# ESP32_C6_Schematic.net
KiCad netlist of a schematic drawn in Altium Designer
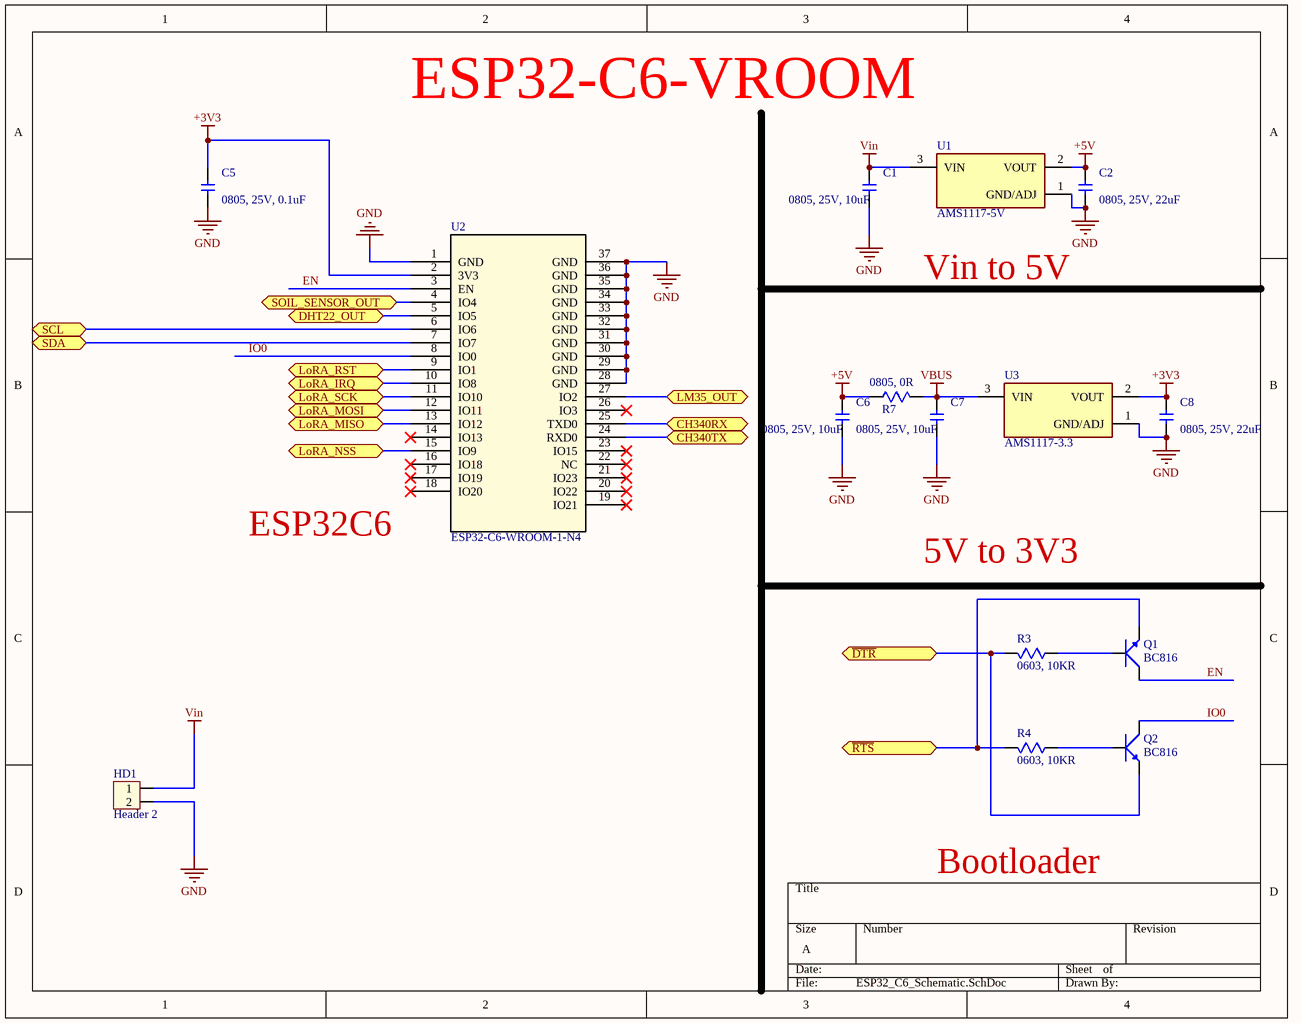
[diagram p0: ESP32_C6_Schematic.SchDoc]

(export (version "E")
  (design (tool "Eeschema 10.0.6"))
  (components
    (comp (ref "C1")
      (value "0805, 25V, 10uF")
      (footprint "C0805")
      (description "C0805")
      (libsource (lib "STM32F103 Blue Pill Library") (part "C0805"))
    )
    (comp (ref "C2")
      (value "0805, 25V, 22uF")
      (footprint "C0805")
      (description "C0805")
      (libsource (lib "STM32F103 Blue Pill Library") (part "C0805"))
    )
    (comp (ref "C5")
      (value "0805, 25V, 0.1uF")
      (footprint "C0805")
      (description "C0805")
      (libsource (lib "STM32F103 Blue Pill Library") (part "C0805"))
    )
    (comp (ref "C6")
      (value "0805, 25V, 10uF")
      (footprint "C0805")
      (description "C0805")
      (libsource (lib "STM32F103 Blue Pill Library") (part "C0805"))
    )
    (comp (ref "C7")
      (value "0805, 25V, 10uF")
      (footprint "C0805")
      (description "C0805")
      (libsource (lib "STM32F103 Blue Pill Library") (part "C0805"))
    )
    (comp (ref "C8")
      (value "0805, 25V, 22uF")
      (footprint "C0805")
      (description "C0805")
      (libsource (lib "STM32F103 Blue Pill Library") (part "C0805"))
    )
    (comp (ref "HD1")
      (value "Header 2")
      (footprint "HED2")
      (description "Header 2 (Green)")
      (libsource (lib "My Library") (part "Hed2"))
    )
    (comp (ref "Q1")
      (value "BC816")
      (footprint "SOT95P237X111-3N")
      (description "Transistor NPN 45V 0.5A hfe160 SOT23 ¦ ON Semiconductor BC817-25LT1G")
      (fields (field (name "MF") "ON Semiconductor") (field (name "MP") "BC817-25LT1G"))
      (libsource (lib "ESP_LoRa_schematic_lib") (part "BC816"))
    )
    (comp (ref "Q2")
      (value "BC816")
      (footprint "SOT95P237X111-3N")
      (description "Transistor NPN 45V 0.5A hfe160 SOT23 ¦ ON Semiconductor BC817-25LT1G")
      (fields (field (name "MF") "ON Semiconductor") (field (name "MP") "BC817-25LT1G"))
      (libsource (lib "ESP_LoRa_schematic_lib") (part "BC816"))
    )
    (comp (ref "R3")
      (value "0603, 10KR")
      (footprint "RES0603")
      (description "R0603")
      (libsource (lib "STM32F103 Blue Pill Library") (part "R0603"))
    )
    (comp (ref "R4")
      (value "0603, 10KR")
      (footprint "RES0603")
      (description "R0603")
      (libsource (lib "STM32F103 Blue Pill Library") (part "R0603"))
    )
    (comp (ref "R7")
      (value "0805, 0R")
      (footprint "C0805")
      (description "R0805")
      (libsource (lib "STM32F103 Blue Pill Library") (part "R0805"))
    )
    (comp (ref "U1")
      (value "AMS1117-5V")
      (footprint "SOT229P700X180-4N")
      (description "Sot223/Pkg 1-Amp 5V-Volt Low Drop Out Voltage Regulatator")
      (fields (field (name "MF") "Advanced Monolithic Systems") (field (name "MP") "AMS1117-3.3"))
      (libsource (lib "ESP_LoRa_schematic_lib") (part "AMS1117-5V"))
    )
    (comp (ref "U2")
      (value "ESP32-C6-WROOM-1-N4")
      (footprint "MOD28_ESP32-C6-WROOM-1_EXP")
      (description "Description")
      (fields (field (name "COPYRIGHT") "Copyright (C) 2025 Ultra Librarian. All rights reserved."))
      (libsource (lib "ESP_LoRa_schematic_lib") (part "ESP32-C6-WROOM-1-N4"))
    )
    (comp (ref "U3")
      (value "AMS1117-3.3")
      (footprint "SOT229P700X180-4N")
      (description "Sot223/Pkg 1-Amp 3.3-Volt Low Drop Out Voltage Regulatator")
      (fields (field (name "MF") "Advanced Monolithic Systems"))
      (libsource (lib "ESP_LoRa_schematic_lib") (part "AMS1117-3.3"))
    )
  )
  (nets
    (net (code "1") (name "+3V3") (class "Default")
      (node (ref "C5") (pin "2") (pinfunction "2_2") (pintype "passive"))
      (node (ref "C8") (pin "2") (pinfunction "2_2") (pintype "passive"))
      (node (ref "U2") (pin "2") (pinfunction "3V3_2") (pintype "passive"))
      (node (ref "U3") (pin "2") (pinfunction "VOUT_2") (pintype "passive"))
    )
    (net (code "2") (name "+5V") (class "Default")
      (node (ref "C2") (pin "2") (pinfunction "2_2") (pintype "passive"))
      (node (ref "C6") (pin "2") (pinfunction "2_2") (pintype "passive"))
      (node (ref "R7") (pin "1") (pinfunction "1_1") (pintype "passive"))
      (node (ref "U1") (pin "2") (pinfunction "VOUT_2") (pintype "passive"))
    )
    (net (code "3") (name "/CH340RX") (class "Default")
      (node (ref "U2") (pin "25") (pinfunction "TXD0_25") (pintype "passive"))
    )
    (net (code "4") (name "/CH340TX") (class "Default")
      (node (ref "U2") (pin "24") (pinfunction "RXD0_24") (pintype "passive"))
    )
    (net (code "5") (name "/DHT22_OUT") (class "Default")
      (node (ref "U2") (pin "5") (pinfunction "IO5_5") (pintype "passive"))
    )
    (net (code "6") (name "/EN") (class "Default")
      (node (ref "Q1") (pin "3") (pinfunction "C_3") (pintype "passive"))
      (node (ref "U2") (pin "3") (pinfunction "EN_3") (pintype "passive"))
    )
    (net (code "7") (name "/IO0") (class "Default")
      (node (ref "Q2") (pin "3") (pinfunction "C_3") (pintype "passive"))
      (node (ref "U2") (pin "8") (pinfunction "IO0_8") (pintype "passive"))
    )
    (net (code "8") (name "/LM35_OUT") (class "Default")
      (node (ref "U2") (pin "27") (pinfunction "IO2_27") (pintype "passive"))
    )
    (net (code "9") (name "/LoRA_IRQ") (class "Default")
      (node (ref "U2") (pin "10") (pinfunction "IO8_10") (pintype "passive"))
    )
    (net (code "10") (name "/LoRA_MISO") (class "Default")
      (node (ref "U2") (pin "13") (pinfunction "IO12_13") (pintype "passive"))
    )
    (net (code "11") (name "/LoRA_MOSI") (class "Default")
      (node (ref "U2") (pin "12") (pinfunction "IO11_12") (pintype "passive"))
    )
    (net (code "12") (name "/LoRA_NSS") (class "Default")
      (node (ref "U2") (pin "15") (pinfunction "IO9_15") (pintype "passive"))
    )
    (net (code "13") (name "/LoRA_RST") (class "Default")
      (node (ref "U2") (pin "9") (pinfunction "IO1_9") (pintype "passive"))
    )
    (net (code "14") (name "/LoRA_SCK") (class "Default")
      (node (ref "U2") (pin "11") (pinfunction "IO10_11") (pintype "passive"))
    )
    (net (code "15") (name "/SCL") (class "Default")
      (node (ref "U2") (pin "6") (pinfunction "IO6_6") (pintype "passive"))
    )
    (net (code "16") (name "/SDA") (class "Default")
      (node (ref "U2") (pin "7") (pinfunction "IO7_7") (pintype "passive"))
    )
    (net (code "17") (name "/SOIL_SENSOR_OUT") (class "Default")
      (node (ref "U2") (pin "4") (pinfunction "IO4_4") (pintype "passive"))
    )
    (net (code "18") (name "/~{DTR}") (class "Default")
      (node (ref "Q2") (pin "2") (pinfunction "E_2") (pintype "passive"))
      (node (ref "R3") (pin "2") (pinfunction "2_2") (pintype "passive"))
    )
    (net (code "19") (name "/~{RTS}") (class "Default")
      (node (ref "Q1") (pin "2") (pinfunction "E_2") (pintype "passive"))
      (node (ref "R4") (pin "2") (pinfunction "2_2") (pintype "passive"))
    )
    (net (code "20") (name "GND") (class "Default")
      (node (ref "C1") (pin "1") (pinfunction "1_1") (pintype "passive"))
      (node (ref "C2") (pin "1") (pinfunction "1_1") (pintype "passive"))
      (node (ref "C5") (pin "1") (pinfunction "1_1") (pintype "passive"))
      (node (ref "C6") (pin "1") (pinfunction "1_1") (pintype "passive"))
      (node (ref "C7") (pin "1") (pinfunction "1_1") (pintype "passive"))
      (node (ref "C8") (pin "1") (pinfunction "1_1") (pintype "passive"))
      (node (ref "HD1") (pin "2") (pinfunction "2_2") (pintype "passive"))
      (node (ref "U1") (pin "1") (pinfunction "GND/ADJ_1") (pintype "passive"))
      (node (ref "U2") (pin "1") (pinfunction "GND_1") (pintype "passive"))
      (node (ref "U2") (pin "28") (pinfunction "GND_28") (pintype "passive"))
      (node (ref "U2") (pin "29") (pinfunction "GND_29") (pintype "passive"))
      (node (ref "U2") (pin "30") (pinfunction "GND_30") (pintype "passive"))
      (node (ref "U2") (pin "31") (pinfunction "GND_31") (pintype "passive"))
      (node (ref "U2") (pin "32") (pinfunction "GND_32") (pintype "passive"))
      (node (ref "U2") (pin "33") (pinfunction "GND_33") (pintype "passive"))
      (node (ref "U2") (pin "34") (pinfunction "GND_34") (pintype "passive"))
      (node (ref "U2") (pin "35") (pinfunction "GND_35") (pintype "passive"))
      (node (ref "U2") (pin "36") (pinfunction "GND_36") (pintype "passive"))
      (node (ref "U2") (pin "37") (pinfunction "GND_37") (pintype "passive"))
      (node (ref "U3") (pin "1") (pinfunction "GND/ADJ_1") (pintype "passive"))
    )
    (net (code "21") (name "Net-(Q1-B)") (class "Default")
      (node (ref "Q1") (pin "1") (pinfunction "B_1") (pintype "passive"))
      (node (ref "R3") (pin "1") (pinfunction "1_1") (pintype "passive"))
    )
    (net (code "22") (name "Net-(Q2-B)") (class "Default")
      (node (ref "Q2") (pin "1") (pinfunction "B_1") (pintype "passive"))
      (node (ref "R4") (pin "1") (pinfunction "1_1") (pintype "passive"))
    )
    (net (code "23") (name "VBUS") (class "Default")
      (node (ref "C7") (pin "2") (pinfunction "2_2") (pintype "passive"))
      (node (ref "R7") (pin "2") (pinfunction "2_2") (pintype "passive"))
      (node (ref "U3") (pin "3") (pinfunction "VIN_3") (pintype "passive"))
    )
    (net (code "24") (name "Vin") (class "Default")
      (node (ref "C1") (pin "2") (pinfunction "2_2") (pintype "passive"))
      (node (ref "HD1") (pin "1") (pinfunction "1_1") (pintype "passive"))
      (node (ref "U1") (pin "3") (pinfunction "VIN_3") (pintype "passive"))
    )
    (net (code "25") (name "unconnected-(U2-IO3-Pad26)") (class "Default")
      (node (ref "U2") (pin "26") (pinfunction "IO3_26") (pintype "passive+no_connect"))
    )
    (net (code "26") (name "unconnected-(U2-IO13-Pad14)") (class "Default")
      (node (ref "U2") (pin "14") (pinfunction "IO13_14") (pintype "passive+no_connect"))
    )
    (net (code "27") (name "unconnected-(U2-IO15-Pad23)") (class "Default")
      (node (ref "U2") (pin "23") (pinfunction "IO15_23") (pintype "passive+no_connect"))
    )
    (net (code "28") (name "unconnected-(U2-IO18-Pad16)") (class "Default")
      (node (ref "U2") (pin "16") (pinfunction "IO18_16") (pintype "passive+no_connect"))
    )
    (net (code "29") (name "unconnected-(U2-IO19-Pad17)") (class "Default")
      (node (ref "U2") (pin "17") (pinfunction "IO19_17") (pintype "passive+no_connect"))
    )
    (net (code "30") (name "unconnected-(U2-IO20-Pad18)") (class "Default")
      (node (ref "U2") (pin "18") (pinfunction "IO20_18") (pintype "passive+no_connect"))
    )
    (net (code "31") (name "unconnected-(U2-IO21-Pad19)") (class "Default")
      (node (ref "U2") (pin "19") (pinfunction "IO21_19") (pintype "passive+no_connect"))
    )
    (net (code "32") (name "unconnected-(U2-IO22-Pad20)") (class "Default")
      (node (ref "U2") (pin "20") (pinfunction "IO22_20") (pintype "passive+no_connect"))
    )
    (net (code "33") (name "unconnected-(U2-IO23-Pad21)") (class "Default")
      (node (ref "U2") (pin "21") (pinfunction "IO23_21") (pintype "passive+no_connect"))
    )
    (net (code "34") (name "unconnected-(U2-NC-Pad22)") (class "Default")
      (node (ref "U2") (pin "22") (pinfunction "NC_22") (pintype "passive+no_connect"))
    )
  )
)
